# Adafruit_TB6612.net
KiCad netlist of a schematic drawn in EAGLE
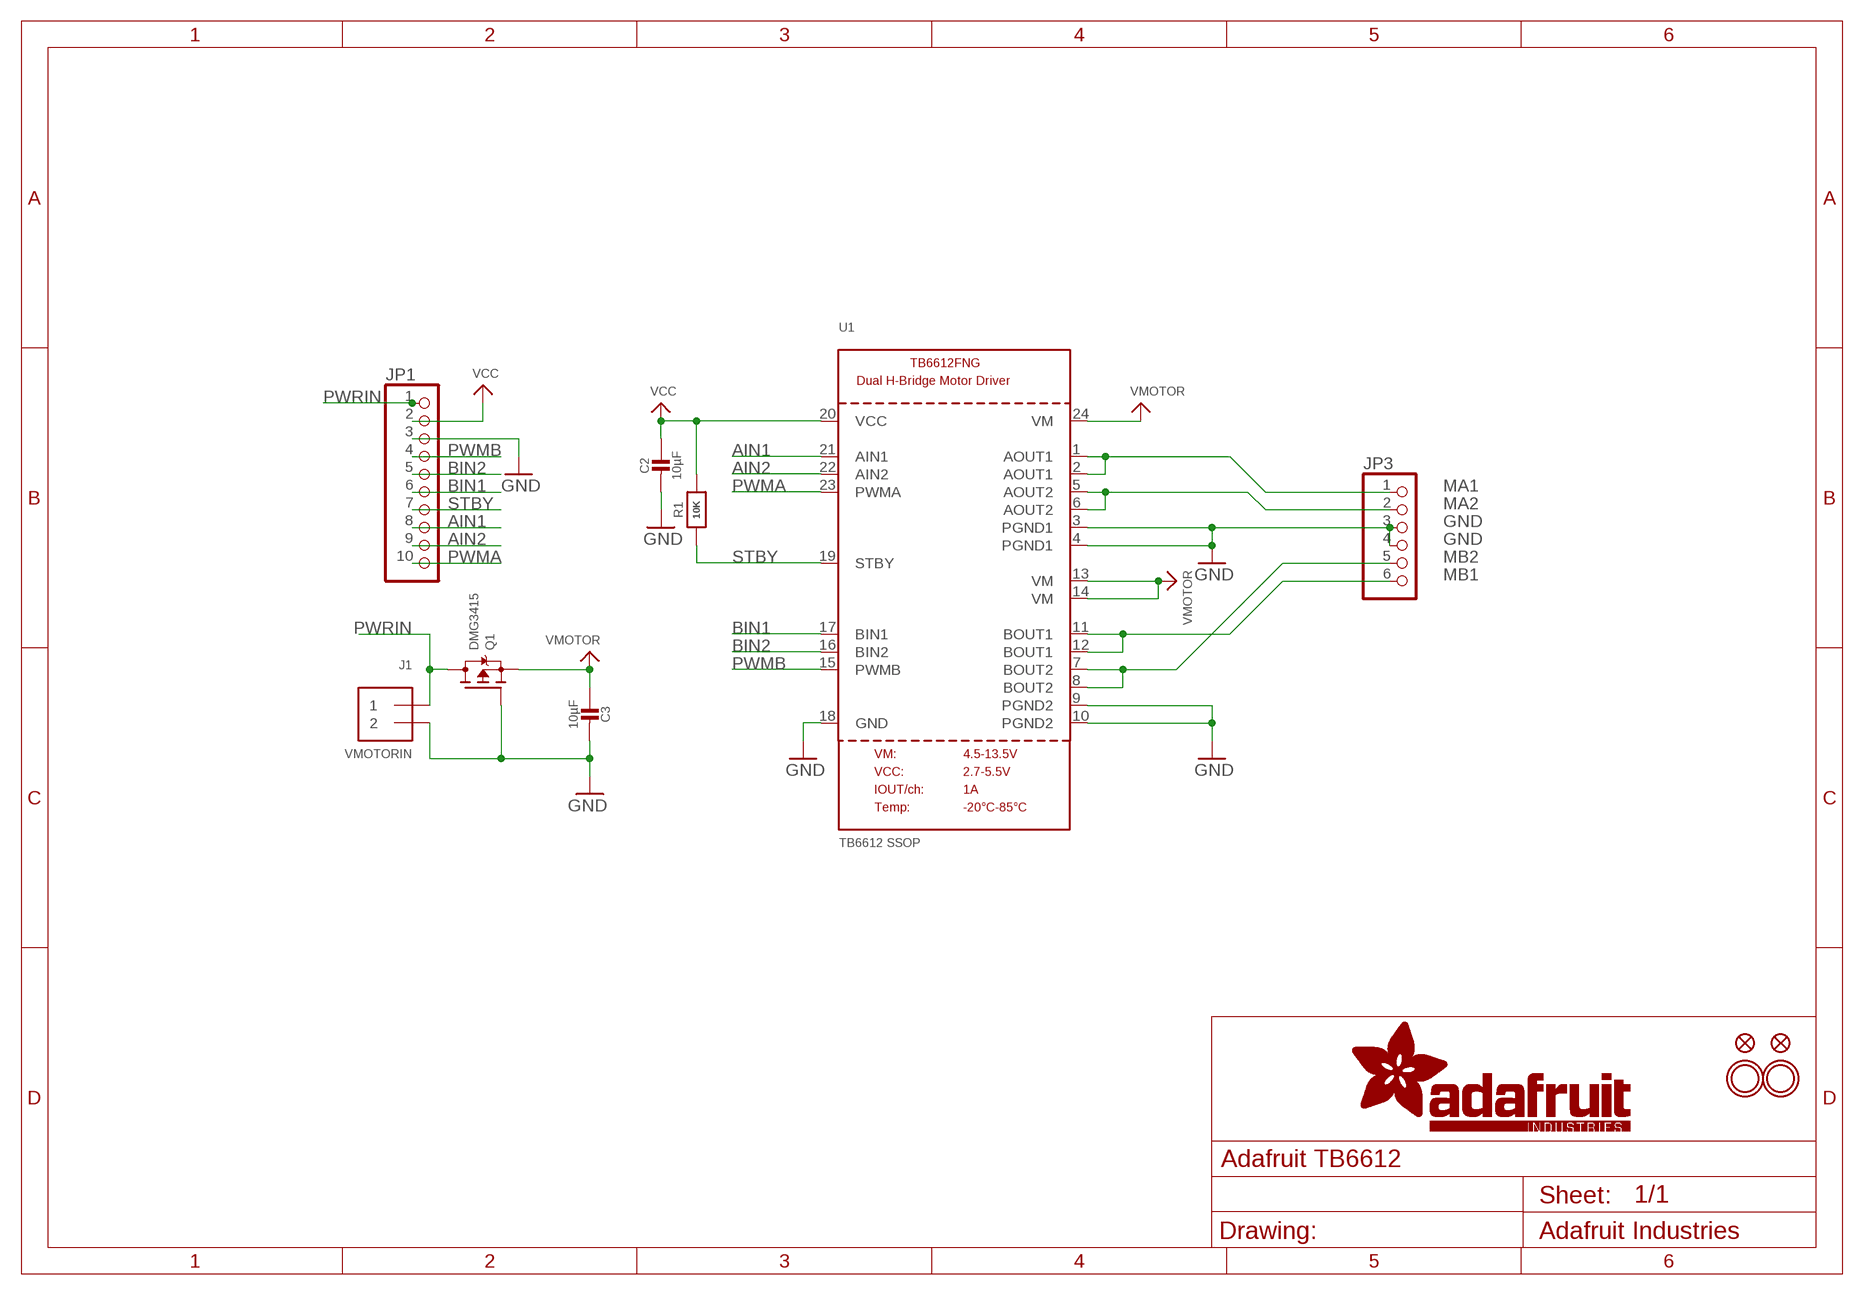
[diagram p0: schematic, sheet 1]

(export (version "E")
  (design (tool "Eeschema 10.0.6"))
  (components
    (comp (ref "C2")
      (value "10µF")
      (footprint "eagle-import:0805-NO")
      (libsource (lib "eagle-import") (part "CAP_CERAMIC0805-NOOUTLINE"))
    )
    (comp (ref "C3")
      (value "10µF")
      (footprint "eagle-import:0805-NO")
      (libsource (lib "eagle-import") (part "CAP_CERAMIC0805-NOOUTLINE"))
    )
    (comp (ref "FID1")
      (value "FIDUCIAL\"\"")
      (footprint "eagle-import:FIDUCIAL_1MM")
      (libsource (lib "eagle-import") (part "FIDUCIAL{dblquote}{dblquote}"))
    )
    (comp (ref "FID2")
      (value "FIDUCIAL\"\"")
      (footprint "eagle-import:FIDUCIAL_1MM")
      (libsource (lib "eagle-import") (part "FIDUCIAL{dblquote}{dblquote}"))
    )
    (comp (ref "J1")
      (value "VMOTORIN")
      (footprint "eagle-import:TERMBLOCK_1X2-3.5MM")
      (libsource (lib "eagle-import") (part "TERMBLOCK_1X2"))
    )
    (comp (ref "JP1")
      (value "HEADER-1X10THICKER")
      (footprint "eagle-import:1X10_ROUND_76")
      (libsource (lib "eagle-import") (part "HEADER-1X10THICKER"))
    )
    (comp (ref "JP3")
      (value "PINHD-1X6CB")
      (footprint "eagle-import:1X06-CLEANBIG")
      (libsource (lib "eagle-import") (part "PINHD-1X6CB"))
    )
    (comp (ref "Q1")
      (value "DMG3415")
      (footprint "eagle-import:SOT23-WIDE")
      (libsource (lib "eagle-import") (part "MOSFET-PWIDE"))
    )
    (comp (ref "R1")
      (value "10K")
      (footprint "eagle-import:0805-NO")
      (libsource (lib "eagle-import") (part "RESISTOR0805_NOOUTLINE"))
    )
    (comp (ref "U$13")
      (value "MOUNTINGHOLE2.5")
      (footprint "eagle-import:MOUNTINGHOLE_2.5_PLATED")
      (libsource (lib "eagle-import") (part "MOUNTINGHOLE2.5"))
    )
    (comp (ref "U$14")
      (value "MOUNTINGHOLE2.5")
      (footprint "eagle-import:MOUNTINGHOLE_2.5_PLATED")
      (libsource (lib "eagle-import") (part "MOUNTINGHOLE2.5"))
    )
    (comp (ref "U1")
      (value "TB6612 SSOP")
      (footprint "eagle-import:SSOP24")
      (libsource (lib "eagle-import") (part "TB6612FNGSSOP"))
    )
  )
  (nets
    (net (code "1") (name "/AIN1") (class "Default")
      (node (ref "JP1") (pin "8") (pinfunction "8_8") (pintype "passive"))
      (node (ref "U1") (pin "21") (pinfunction "AIN1_21") (pintype "input"))
    )
    (net (code "2") (name "/AIN2") (class "Default")
      (node (ref "JP1") (pin "9") (pinfunction "9_9") (pintype "passive"))
      (node (ref "U1") (pin "22") (pinfunction "AIN2_22") (pintype "input"))
    )
    (net (code "3") (name "/BIN1") (class "Default")
      (node (ref "JP1") (pin "6") (pinfunction "6_6") (pintype "passive"))
      (node (ref "U1") (pin "17") (pinfunction "BIN1_17") (pintype "input"))
    )
    (net (code "4") (name "/BIN2") (class "Default")
      (node (ref "JP1") (pin "5") (pinfunction "5_5") (pintype "passive"))
      (node (ref "U1") (pin "16") (pinfunction "BIN2_16") (pintype "input"))
    )
    (net (code "5") (name "/MA1") (class "Default")
      (node (ref "JP3") (pin "1") (pinfunction "1_1") (pintype "passive"))
      (node (ref "U1") (pin "1") (pinfunction "AOUT1_1") (pintype "output"))
      (node (ref "U1") (pin "2") (pinfunction "AOUT1_2") (pintype "output"))
    )
    (net (code "6") (name "/MA2") (class "Default")
      (node (ref "JP3") (pin "2") (pinfunction "2_2") (pintype "passive"))
      (node (ref "U1") (pin "5") (pinfunction "AOUT2_5") (pintype "output"))
      (node (ref "U1") (pin "6") (pinfunction "AOUT2_6") (pintype "output"))
    )
    (net (code "7") (name "/MB1") (class "Default")
      (node (ref "JP3") (pin "6") (pinfunction "6_6") (pintype "passive"))
      (node (ref "U1") (pin "11") (pinfunction "BOUT1_11") (pintype "output"))
      (node (ref "U1") (pin "12") (pinfunction "BOUT1_12") (pintype "output"))
    )
    (net (code "8") (name "/MB2") (class "Default")
      (node (ref "JP3") (pin "5") (pinfunction "5_5") (pintype "passive"))
      (node (ref "U1") (pin "7") (pinfunction "BOUT2_7") (pintype "output"))
      (node (ref "U1") (pin "8") (pinfunction "BOUT2_8") (pintype "output"))
    )
    (net (code "9") (name "/PWMA") (class "Default")
      (node (ref "JP1") (pin "10") (pinfunction "10_10") (pintype "passive"))
      (node (ref "U1") (pin "23") (pinfunction "PWMA_23") (pintype "input"))
    )
    (net (code "10") (name "/PWMB") (class "Default")
      (node (ref "JP1") (pin "4") (pinfunction "4_4") (pintype "passive"))
      (node (ref "U1") (pin "15") (pinfunction "PWMB_15") (pintype "input"))
    )
    (net (code "11") (name "/PWRIN") (class "Default")
      (node (ref "J1") (pin "1") (pinfunction "1_1") (pintype "passive"))
      (node (ref "JP1") (pin "1") (pinfunction "1_1") (pintype "passive"))
      (node (ref "Q1") (pin "3") (pinfunction "D_3") (pintype "passive"))
    )
    (net (code "12") (name "/STBY") (class "Default")
      (node (ref "JP1") (pin "7") (pinfunction "7_7") (pintype "passive"))
      (node (ref "R1") (pin "1") (pinfunction "1_1") (pintype "passive"))
      (node (ref "U1") (pin "19") (pinfunction "STBY_19") (pintype "input"))
    )
    (net (code "13") (name "GND") (class "Default")
      (node (ref "C2") (pin "2") (pinfunction "2_2") (pintype "passive"))
      (node (ref "C3") (pin "2") (pinfunction "2_2") (pintype "passive"))
      (node (ref "J1") (pin "2") (pinfunction "2_2") (pintype "passive"))
      (node (ref "JP1") (pin "3") (pinfunction "3_3") (pintype "passive"))
      (node (ref "JP3") (pin "3") (pinfunction "3_3") (pintype "passive"))
      (node (ref "JP3") (pin "4") (pinfunction "4_4") (pintype "passive"))
      (node (ref "Q1") (pin "1") (pinfunction "G_1") (pintype "passive"))
      (node (ref "U1") (pin "10") (pinfunction "PGND2_10") (pintype "power_in"))
      (node (ref "U1") (pin "18") (pinfunction "GND_18") (pintype "power_in"))
      (node (ref "U1") (pin "3") (pinfunction "PGND1_3") (pintype "power_in"))
      (node (ref "U1") (pin "4") (pinfunction "PGND1_4") (pintype "power_in"))
      (node (ref "U1") (pin "9") (pinfunction "PGND2_9") (pintype "power_in"))
    )
    (net (code "14") (name "VCC") (class "Default")
      (node (ref "C2") (pin "1") (pinfunction "1_1") (pintype "passive"))
      (node (ref "JP1") (pin "2") (pinfunction "2_2") (pintype "passive"))
      (node (ref "R1") (pin "2") (pinfunction "2_2") (pintype "passive"))
      (node (ref "U1") (pin "20") (pinfunction "VCC_20") (pintype "power_in"))
    )
    (net (code "15") (name "VMOTOR") (class "Default")
      (node (ref "C3") (pin "1") (pinfunction "1_1") (pintype "passive"))
      (node (ref "Q1") (pin "2") (pinfunction "S_2") (pintype "passive"))
      (node (ref "U1") (pin "13") (pinfunction "VM_13") (pintype "power_in"))
      (node (ref "U1") (pin "14") (pinfunction "VM_14") (pintype "power_in"))
      (node (ref "U1") (pin "24") (pinfunction "VM_24") (pintype "power_in"))
    )
  )
)
